# Koruma.net
KiCad netlist of a schematic drawn in Altium Designer
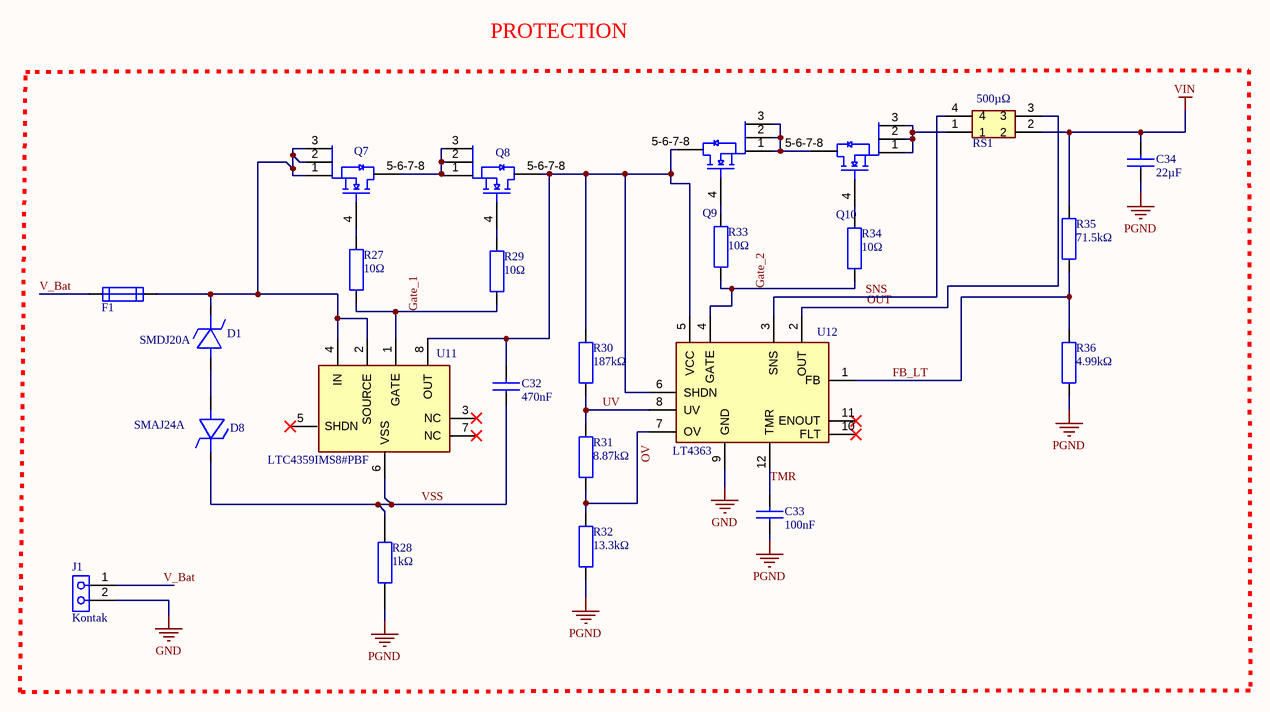
[diagram p0: Koruma.SchDoc]

(export (version "E")
  (design (tool "Eeschema 10.0.6"))
  (components
    (comp (ref "C32")
      (value "470nF")
      (footprint "CAP 0603")
      (description "0612/0805/1206 Feedthru Ceramic Capacitors 1206 50V 47000pF")
      (fields
        (field (name "MANUFACTURER") "TAIYO YUDEN")
        (field (name "MANUFACTURER PART NUMBER") "MCASU168SB7474KTCA01")
      )
      (libsource (lib "UAV") (part "W3F15C4738AT1F"))
    )
    (comp (ref "C33")
      (value "100nF")
      (footprint "CAP 0402")
      (description "16V 100nF X7R ±10% 0402 Multilayer Ceramic Capacitors MLCC - SMD/SMT ROHS")
      (fields
        (field (name "MANUFACTURER") "Murata")
        (field (name "MANUFACTURER PART NUMBER") "GRM155R71C104KA88D")
      )
      (libsource (lib "UAV") (part "GRM155R71C104KA88D"))
    )
    (comp (ref "C34")
      (value "22µF")
      (footprint "CAP 2220")
      (description "50V 22uF X7R 卤20% 2220 Multilayer Ceramic Capacitors MLCC - SMD/SMT ROHS")
      (fields
        (field (name "MANUFACTURER") "TDK")
        (field (name "MANUFACTURER PART NUMBER") "C5750X7R1H226M250KB")
      )
      (libsource (lib "UAV") (part "C5750X7R1H226M250KB"))
    )
    (comp (ref "D1")
      (value "SMDJ20A")
      (footprint "SMC (DO-214AB)")
      (description "SMDJ Series 20 V 3000 W Surface Mount Uni-Directional TVS Diode - DO-214AB")
      (fields (field (name "MANUFACTURER") "Littelfuse"))
      (libsource (lib "UAV") (part "SMDJ20A"))
    )
    (comp (ref "D8")
      (value "SMAJ24A")
      (footprint "SMA (DO-214AC)")
      (description "SMAJ Series 400 W 24 V Uni-Directional Surface Mount TVS Diode - DO-214AC")
      (fields (field (name "MANUFACTURER") "Littelfuse"))
      (libsource (lib "UAV") (part "SMAJ24A"))
    )
    (comp (ref "F1")
      (value "SF-3812F6000T-2")
      (footprint "SF-3812F6000T-2")
      (description "SMD Fuse, Fast Acting, 60 A, 250 VAC, 100 VDC, 3812 [10030 Metric], SF-3812F-T")
      (fields (field (name "MANUFACTURER") "Bourns"))
      (libsource (lib "UAV") (part "SF-3812F6000T-2"))
    )
    (comp (ref "J1")
      (value "Kontak")
      (footprint "TB 2pin")
      (libsource (lib "TIDA_00620") (part "Terminal Block - 2pin"))
    )
    (comp (ref "Q7")
      (value "BSC010N04LSI")
      (footprint "SON 5X6")
      (description "Transistor: N-MOSFET; unipolar; 40V; 100A; 139W; PG-TDSON-8")
      (fields
        (field (name "MANUFACTURER") "Infineon")
        (field (name "MANUFACTURER PART NUMBER") "BSC010N04LSIATMA1")
      )
      (libsource (lib "UAV") (part "BSC010N04LSI"))
    )
    (comp (ref "Q8")
      (value "BSC010N04LSI")
      (footprint "SON 5X6")
      (description "Transistor: N-MOSFET; unipolar; 40V; 100A; 139W; PG-TDSON-8")
      (fields
        (field (name "MANUFACTURER") "Infineon")
        (field (name "MANUFACTURER PART NUMBER") "BSC010N04LSIATMA1")
      )
      (libsource (lib "UAV") (part "BSC010N04LSI"))
    )
    (comp (ref "Q9")
      (value "BSC010N04LSI")
      (footprint "SON 5X6")
      (description "Transistor: N-MOSFET; unipolar; 40V; 100A; 139W; PG-TDSON-8")
      (fields
        (field (name "MANUFACTURER") "Infineon")
        (field (name "MANUFACTURER PART NUMBER") "BSC010N04LSIATMA1")
      )
      (libsource (lib "UAV") (part "BSC010N04LSI"))
    )
    (comp (ref "Q10")
      (value "BSC010N04LSI")
      (footprint "SON 5X6")
      (description "Transistor: N-MOSFET; unipolar; 40V; 100A; 139W; PG-TDSON-8")
      (fields
        (field (name "MANUFACTURER") "Infineon")
        (field (name "MANUFACTURER PART NUMBER") "BSC010N04LSIATMA1")
      )
      (libsource (lib "UAV") (part "BSC010N04LSI"))
    )
    (comp (ref "R27")
      (value "10Ω")
      (footprint "SR0805FR-7W10RL")
      (description "Res Thick Film 0805 10 Ohm 1% 0.25W(1/4W) ±200ppm/C Pad SMD Automotive T/R")
      (fields
        (field (name "MANUFACTURER") "Yageo Group")
        (field (name "MANUFACTURER PART NUMBER") "SR0805FR-7W10RL")
      )
      (libsource (lib "UAV") (part "SR0805FR-7W10RL"))
    )
    (comp (ref "R28")
      (value "1kΩ")
      (footprint "RES 1206")
      (fields
        (field (name "MANUFACTURER") "Yageo Group")
        (field (name "MANUFACTURER PART NUMBER") "SR1206FR-071KL")
        (field (name "TOLERANCE") "1%")
      )
      (libsource (lib "UAV") (part "SR1206FR-071KL"))
    )
    (comp (ref "R29")
      (value "10Ω")
      (footprint "SR0805FR-7W10RL")
      (description "Res Thick Film 0805 10 Ohm 1% 0.25W(1/4W) ±200ppm/C Pad SMD Automotive T/R")
      (fields
        (field (name "MANUFACTURER") "Yageo Group")
        (field (name "MANUFACTURER PART NUMBER") "SR0805FR-7W10RL")
      )
      (libsource (lib "UAV") (part "SR0805FR-7W10RL"))
    )
    (comp (ref "R30")
      (value "187kΩ")
      (footprint "RES 1206")
      (description "Res Thick Film 0805 187K Ohm 1% 0.125W(1/8W) ±100ppm/C Pad SMD T/R")
      (fields
        (field (name "MANUFACTURER") "Yageo Group")
        (field (name "MANUFACTURER PART NUMBER") "RC0805FR-07187KL")
      )
      (libsource (lib "UAV") (part "RC0805FR-07187KL"))
    )
    (comp (ref "R31")
      (value "8.87kΩ")
      (footprint "RES 1206")
      (description "Res Thick Film 0805 8.87K Ohm 1% 0.125W(1/8W) ±100ppm/C Pad SMD T/R")
      (fields
        (field (name "MANUFACTURER") "Yageo Group")
        (field (name "MANUFACTURER PART NUMBER") "RC0805FR-078K87L")
      )
      (libsource (lib "UAV") (part "RC0805FR-078K87L"))
    )
    (comp (ref "R32")
      (value "13.3kΩ")
      (footprint "RES 1206")
      (description "Res Thick Film 0805 13.3K Ohm 1% 0.125W(1/8W) ±100ppm/C Pad SMD T/R")
      (fields
        (field (name "MANUFACTURER") "Yageo Group")
        (field (name "MANUFACTURER PART NUMBER") "RC0805FR-0713K3L")
      )
      (libsource (lib "UAV") (part "RC0805FR-0713K3L"))
    )
    (comp (ref "R33")
      (value "10Ω")
      (footprint "SR0805FR-7W10RL")
      (description "Res Thick Film 0805 10 Ohm 1% 0.25W(1/4W) ±200ppm/C Pad SMD Automotive T/R")
      (fields
        (field (name "MANUFACTURER") "Yageo Group")
        (field (name "MANUFACTURER PART NUMBER") "SR0805FR-7W10RL")
      )
      (libsource (lib "UAV") (part "SR0805FR-7W10RL"))
    )
    (comp (ref "R34")
      (value "10Ω")
      (footprint "SR0805FR-7W10RL")
      (description "Res Thick Film 0805 10 Ohm 1% 0.25W(1/4W) ±200ppm/C Pad SMD Automotive T/R")
      (fields
        (field (name "MANUFACTURER") "Yageo Group")
        (field (name "MANUFACTURER PART NUMBER") "SR0805FR-7W10RL")
      )
      (libsource (lib "UAV") (part "SR0805FR-7W10RL"))
    )
    (comp (ref "R35")
      (value "71.5kΩ")
      (footprint "RES 0603")
      (description "Res Thick Film 0603 71.5K Ohm 1% 0.1W(1/10W) ±100ppm/C Pad SMD T/R")
      (fields
        (field (name "MANUFACTURER") "Yageo Group")
        (field (name "MANUFACTURER PART NUMBER") "RC0603FR-0771K5L")
      )
      (libsource (lib "UAV") (part "RC0603FR-0771K5L"))
    )
    (comp (ref "R36")
      (value "4.99kΩ")
      (footprint "RES 0402")
      (description "Res Thick Film 0402 4.99K Ohm 1% 0.1W(1/10W) ±100ppm/C Pad SMD Automotive T/R")
      (fields
        (field (name "MANUFACTURER") "Panasonic")
        (field (name "MANUFACTURER PART NUMBER") "ERJ2RKF4991X")
      )
      (libsource (lib "UAV") (part "ERJ-2RKF4991X"))
    )
    (comp (ref "RS1")
      (value "500µΩ")
      (footprint "SR_4026")
      (description "Res Metal Strip 4026 0.0005 Ohm 1% 7W ±75ppm/C Metal Pad SMD Automotive T/R")
      (fields
        (field (name "MANUFACTURER") "Vishay")
        (field (name "MANUFACTURER PART NUMBER") "WSLP4026L5000FEA")
      )
      (libsource (lib "UAV") (part "WSLP4026L5000FEA"))
    )
    (comp (ref "U11")
      (value "LTC4359IMS8#PBF")
      (footprint "MSOP-8")
      (description "OR Controller N-Channel Single Automotive 8-Pin MSOP Tube / IC OR CTRLR N+1 8MSOP")
      (fields (field (name "MANUFACTURER") "Analog Devices"))
      (libsource (lib "UAV") (part "LTC4359IMS8#PBF"))
    )
    (comp (ref "U12")
      (value "LT4363")
      (footprint "MSOP-12")
      (description "Circuit Protection Misc High Voltage Surge Stopper with Current Limit")
      (fields
        (field (name "MANUFACTURER") "Analog Devices")
        (field (name "MANUFACTURER PART NUMBER") "LT4363MPMS-1#TRPBF")
      )
      (libsource (lib "UAV") (part "LT4363IMS-2#PBF"))
    )
  )
  (nets
    (net (code "1") (name "/FB_LT") (class "Default")
      (node (ref "R35") (pin "1") (pinfunction "1_1") (pintype "passive"))
      (node (ref "R36") (pin "2") (pinfunction "2_2") (pintype "passive"))
      (node (ref "U12") (pin "1") (pinfunction "FB_1") (pintype "passive"))
    )
    (net (code "2") (name "/Gate_1") (class "Default")
      (node (ref "R27") (pin "1") (pinfunction "1_1") (pintype "passive"))
      (node (ref "R29") (pin "1") (pinfunction "1_1") (pintype "passive"))
      (node (ref "U11") (pin "1") (pinfunction "GATE_1") (pintype "passive"))
    )
    (net (code "3") (name "/Gate_2") (class "Default")
      (node (ref "R33") (pin "1") (pinfunction "1_1") (pintype "passive"))
      (node (ref "R34") (pin "1") (pinfunction "1_1") (pintype "passive"))
      (node (ref "U12") (pin "4") (pinfunction "GATE_4") (pintype "passive"))
    )
    (net (code "4") (name "/OUT") (class "Default")
      (node (ref "RS1") (pin "3") (pinfunction "3_3") (pintype "passive"))
      (node (ref "U12") (pin "2") (pinfunction "OUT_2") (pintype "passive"))
    )
    (net (code "5") (name "/OV") (class "Default")
      (node (ref "R31") (pin "1") (pinfunction "1_1") (pintype "passive"))
      (node (ref "R32") (pin "2") (pinfunction "2_2") (pintype "passive"))
      (node (ref "U12") (pin "7") (pinfunction "OV_7") (pintype "passive"))
    )
    (net (code "6") (name "/SNS") (class "Default")
      (node (ref "RS1") (pin "4") (pinfunction "4_4") (pintype "passive"))
      (node (ref "U12") (pin "3") (pinfunction "SNS_3") (pintype "passive"))
    )
    (net (code "7") (name "/TMR") (class "Default")
      (node (ref "C33") (pin "2") (pinfunction "2_2") (pintype "passive"))
      (node (ref "U12") (pin "12") (pinfunction "TMR_12") (pintype "passive"))
    )
    (net (code "8") (name "/UV") (class "Default")
      (node (ref "R30") (pin "2") (pinfunction "2_2") (pintype "passive"))
      (node (ref "R31") (pin "2") (pinfunction "2_2") (pintype "passive"))
      (node (ref "U12") (pin "8") (pinfunction "UV_8") (pintype "passive"))
    )
    (net (code "9") (name "/VSS") (class "Default")
      (node (ref "C32") (pin "1") (pinfunction "1_1") (pintype "passive"))
      (node (ref "D8") (pin "1") (pinfunction "1_1") (pintype "passive"))
      (node (ref "R28") (pin "2") (pinfunction "2_2") (pintype "passive"))
      (node (ref "U11") (pin "6") (pinfunction "VSS_6") (pintype "passive"))
    )
    (net (code "10") (name "/V_Bat") (class "Default")
      (node (ref "F1") (pin "1") (pinfunction "1_1") (pintype "passive"))
      (node (ref "J1") (pin "1") (pinfunction "0_1") (pintype "passive"))
    )
    (net (code "11") (name "GND") (class "Default")
      (node (ref "J1") (pin "2") (pinfunction "1_2") (pintype "passive"))
      (node (ref "U12") (pin "9") (pinfunction "GND_9") (pintype "passive"))
    )
    (net (code "12") (name "Net-(D1-Pad2)") (class "Default")
      (node (ref "D1") (pin "2") (pinfunction "2_2") (pintype "passive"))
      (node (ref "D8") (pin "2") (pinfunction "2_2") (pintype "passive"))
    )
    (net (code "13") (name "Net-(Q7-D)") (class "Default")
      (node (ref "Q7") (pin "5-6-7-8") (pinfunction "D_5-6-7-8") (pintype "passive"))
      (node (ref "Q8") (pin "1") (pinfunction "S_1") (pintype "passive"))
      (node (ref "Q8") (pin "2") (pinfunction "S_2") (pintype "passive"))
      (node (ref "Q8") (pin "3") (pinfunction "S_3") (pintype "passive"))
    )
    (net (code "14") (name "Net-(Q7-G)") (class "Default")
      (node (ref "Q7") (pin "4") (pinfunction "G_4") (pintype "passive"))
      (node (ref "R27") (pin "2") (pinfunction "2_2") (pintype "passive"))
    )
    (net (code "15") (name "Net-(Q8-D)") (class "Default")
      (node (ref "C32") (pin "2") (pinfunction "2_2") (pintype "passive"))
      (node (ref "Q8") (pin "5-6-7-8") (pinfunction "D_5-6-7-8") (pintype "passive"))
      (node (ref "Q9") (pin "5-6-7-8") (pinfunction "D_5-6-7-8") (pintype "passive"))
      (node (ref "R30") (pin "1") (pinfunction "1_1") (pintype "passive"))
      (node (ref "U11") (pin "8") (pinfunction "OUT_8") (pintype "passive"))
      (node (ref "U12") (pin "5") (pinfunction "VCC_5") (pintype "passive"))
      (node (ref "U12") (pin "6") (pinfunction "SHDN_6") (pintype "passive"))
    )
    (net (code "16") (name "Net-(Q8-G)") (class "Default")
      (node (ref "Q8") (pin "4") (pinfunction "G_4") (pintype "passive"))
      (node (ref "R29") (pin "2") (pinfunction "2_2") (pintype "passive"))
    )
    (net (code "17") (name "Net-(Q9-G)") (class "Default")
      (node (ref "Q9") (pin "4") (pinfunction "G_4") (pintype "passive"))
      (node (ref "R33") (pin "2") (pinfunction "2_2") (pintype "passive"))
    )
    (net (code "18") (name "Net-(Q10-D)") (class "Default")
      (node (ref "Q10") (pin "5-6-7-8") (pinfunction "D_5-6-7-8") (pintype "passive"))
      (node (ref "Q9") (pin "1") (pinfunction "S_1") (pintype "passive"))
      (node (ref "Q9") (pin "2") (pinfunction "S_2") (pintype "passive"))
      (node (ref "Q9") (pin "3") (pinfunction "S_3") (pintype "passive"))
    )
    (net (code "19") (name "Net-(Q10-G)") (class "Default")
      (node (ref "Q10") (pin "4") (pinfunction "G_4") (pintype "passive"))
      (node (ref "R34") (pin "2") (pinfunction "2_2") (pintype "passive"))
    )
    (net (code "20") (name "Net-(Q10-S-Pad1)") (class "Default")
      (node (ref "Q10") (pin "1") (pinfunction "S_1") (pintype "passive"))
      (node (ref "Q10") (pin "2") (pinfunction "S_2") (pintype "passive"))
      (node (ref "Q10") (pin "3") (pinfunction "S_3") (pintype "passive"))
      (node (ref "RS1") (pin "1") (pinfunction "1_1") (pintype "passive"))
    )
    (net (code "21") (name "Net-(U11-IN)") (class "Default")
      (node (ref "D1") (pin "1") (pinfunction "1_1") (pintype "passive"))
      (node (ref "F1") (pin "2") (pinfunction "2_2") (pintype "passive"))
      (node (ref "Q7") (pin "1") (pinfunction "S_1") (pintype "passive"))
      (node (ref "Q7") (pin "2") (pinfunction "S_2") (pintype "passive"))
      (node (ref "Q7") (pin "3") (pinfunction "S_3") (pintype "passive"))
      (node (ref "U11") (pin "2") (pinfunction "SOURCE_2") (pintype "passive"))
      (node (ref "U11") (pin "4") (pinfunction "IN_4") (pintype "passive"))
    )
    (net (code "22") (name "PGND") (class "Default")
      (node (ref "C33") (pin "1") (pinfunction "1_1") (pintype "passive"))
      (node (ref "C34") (pin "1") (pinfunction "1_1") (pintype "passive"))
      (node (ref "R28") (pin "1") (pinfunction "1_1") (pintype "passive"))
      (node (ref "R32") (pin "1") (pinfunction "1_1") (pintype "passive"))
      (node (ref "R36") (pin "1") (pinfunction "1_1") (pintype "passive"))
    )
    (net (code "23") (name "VIN") (class "Default")
      (node (ref "C34") (pin "2") (pinfunction "2_2") (pintype "passive"))
      (node (ref "R35") (pin "2") (pinfunction "2_2") (pintype "passive"))
      (node (ref "RS1") (pin "2") (pinfunction "2_2") (pintype "passive"))
    )
    (net (code "24") (name "unconnected-(U11-NC-Pad3)") (class "Default")
      (node (ref "U11") (pin "3") (pinfunction "NC_3") (pintype "passive+no_connect"))
    )
    (net (code "25") (name "unconnected-(U11-NC-Pad7)") (class "Default")
      (node (ref "U11") (pin "7") (pinfunction "NC_7") (pintype "passive+no_connect"))
    )
    (net (code "26") (name "unconnected-(U11-SHDN-Pad5)") (class "Default")
      (node (ref "U11") (pin "5") (pinfunction "SHDN_5") (pintype "passive+no_connect"))
    )
    (net (code "27") (name "unconnected-(U12-ENOUT-Pad11)") (class "Default")
      (node (ref "U12") (pin "11") (pinfunction "ENOUT_11") (pintype "passive+no_connect"))
    )
    (net (code "28") (name "unconnected-(U12-FLT-Pad10)") (class "Default")
      (node (ref "U12") (pin "10") (pinfunction "FLT_10") (pintype "passive+no_connect"))
    )
  )
)
